# Platine_Messgeraet_Frank_20220912-v004.net
KiCad netlist of a schematic drawn in EAGLE
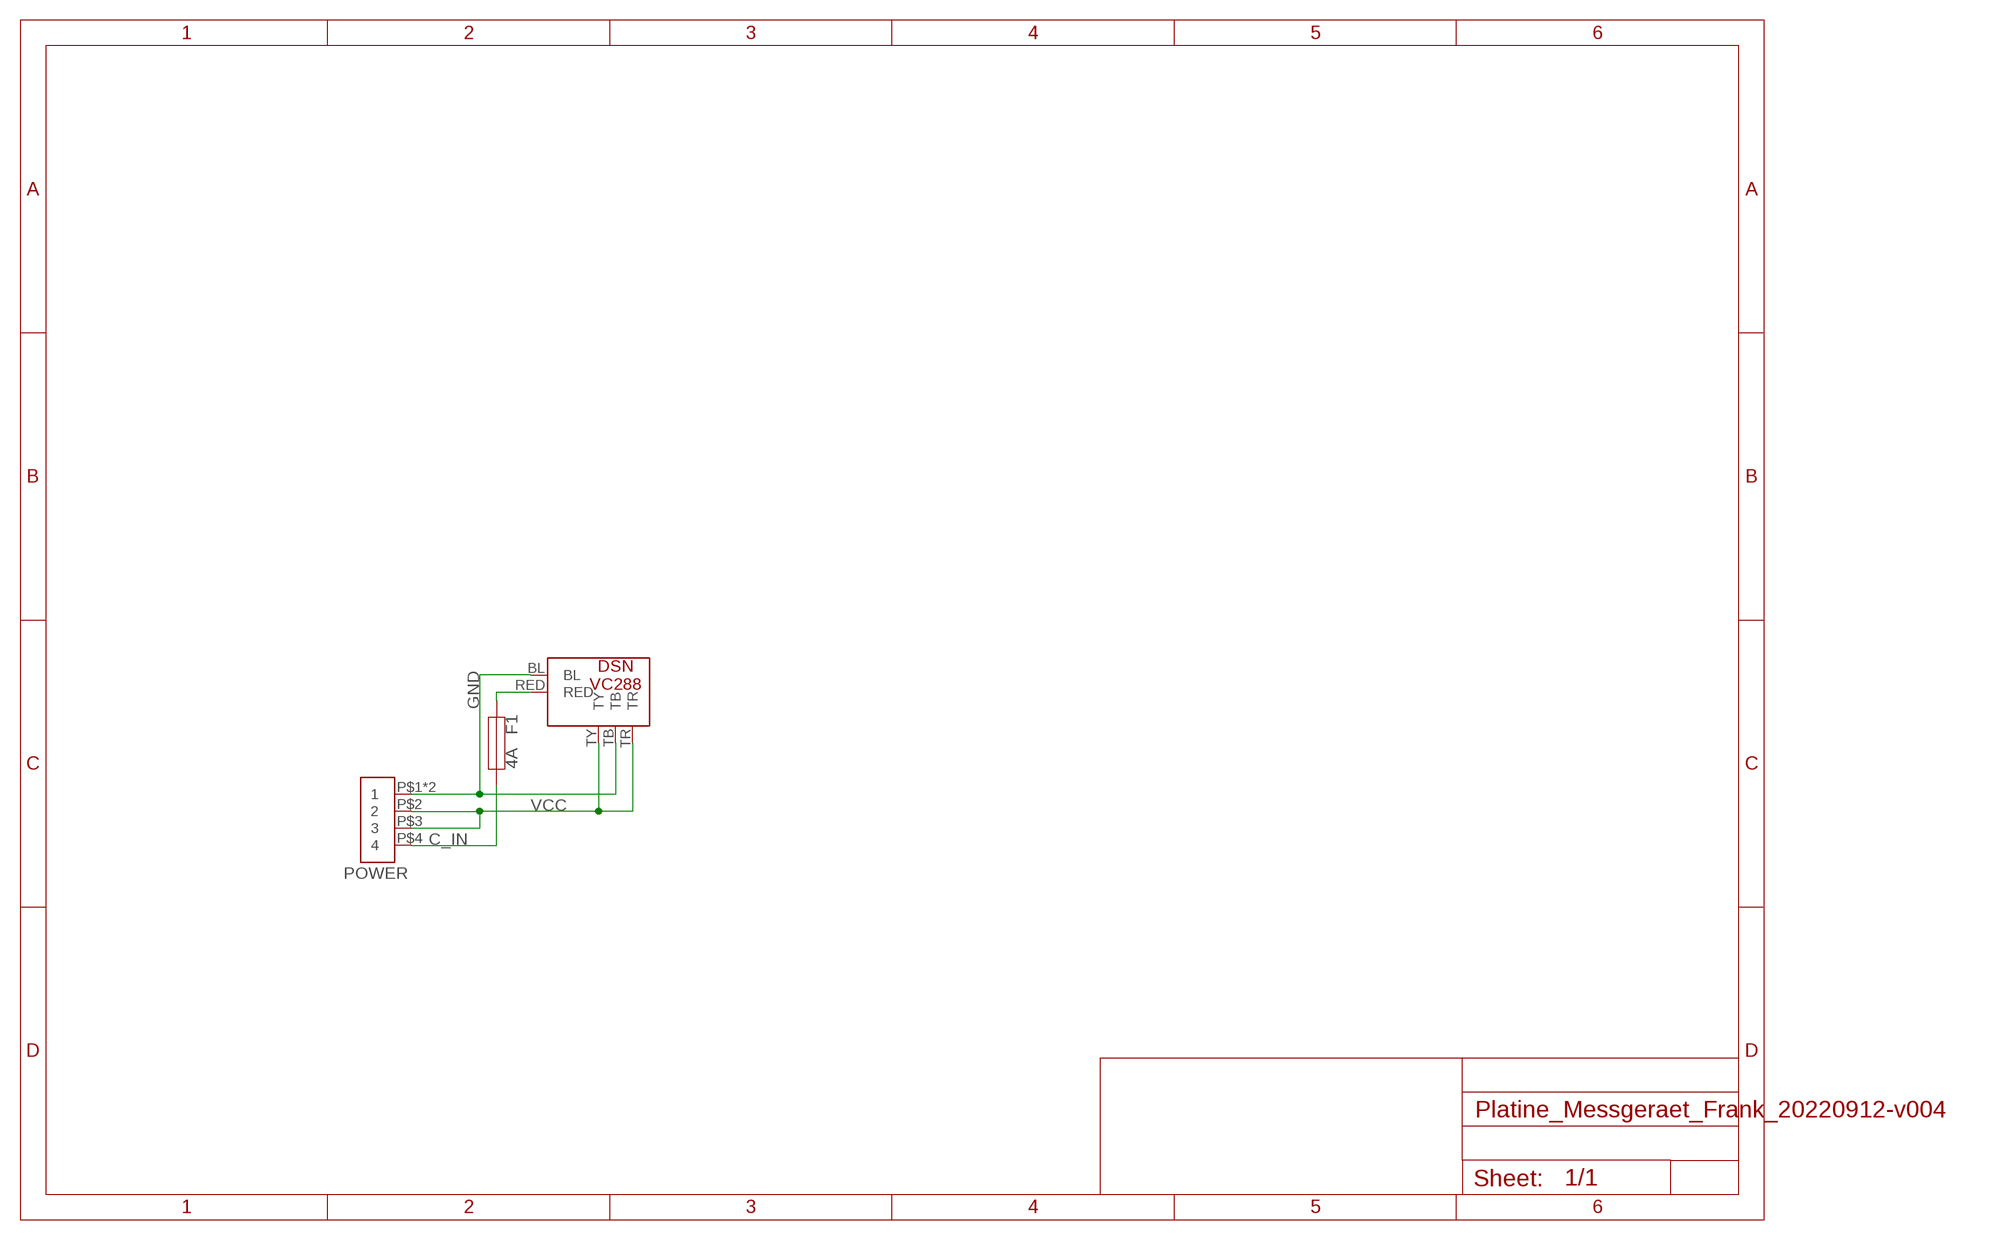
[diagram p0: schematic, sheet 1]

(export (version "E")
  (design (tool "Eeschema 10.0.6"))
  (components
    (comp (ref "F1")
      (value "4A")
      (footprint "eagle-import:FUSE_5X20-L")
      (libsource (lib "eagle-import") (part "FUSES90"))
    )
    (comp (ref "POWER")
      (value "CB-SCREW-4PF")
      (footprint "eagle-import:CTB932VD-4F")
      (libsource (lib "eagle-import") (part "CB-SCREW-4PF"))
    )
    (comp (ref "U$1")
      (value "DSN-VC288")
      (footprint "eagle-import:DSN-VC288")
      (libsource (lib "eagle-import") (part "DSN-VC288"))
    )
  )
  (nets
    (net (code "1") (name "/C_IN") (class "Default")
      (node (ref "F1") (pin "1") (pinfunction "1_1") (pintype "bidirectional"))
      (node (ref "POWER") (pin "P$4") (pinfunction "4_P$4") (pintype "bidirectional"))
    )
    (net (code "2") (name "/GND") (class "Default")
      (node (ref "POWER") (pin "P$1") (pinfunction "1_P$1") (pintype "bidirectional"))
      (node (ref "POWER") (pin "P$5") (pinfunction "1_P$5") (pintype "bidirectional"))
      (node (ref "U$1") (pin "BL") (pinfunction "BL_BL") (pintype "bidirectional"))
      (node (ref "U$1") (pin "TB") (pinfunction "TB_TB") (pintype "bidirectional"))
    )
    (net (code "3") (name "/VCC") (class "Default")
      (node (ref "POWER") (pin "P$2") (pinfunction "2_P$2") (pintype "bidirectional"))
      (node (ref "POWER") (pin "P$3") (pinfunction "3_P$3") (pintype "bidirectional"))
      (node (ref "U$1") (pin "TR") (pinfunction "TR_TR") (pintype "bidirectional"))
      (node (ref "U$1") (pin "TY") (pinfunction "TY_TY") (pintype "bidirectional"))
    )
    (net (code "4") (name "Net-(F1-Pad2)") (class "Default")
      (node (ref "F1") (pin "2") (pinfunction "2_2") (pintype "bidirectional"))
      (node (ref "U$1") (pin "RED") (pinfunction "RED_RED") (pintype "bidirectional"))
    )
  )
)
